# EndStop.net
KiCad netlist of a schematic drawn in EAGLE
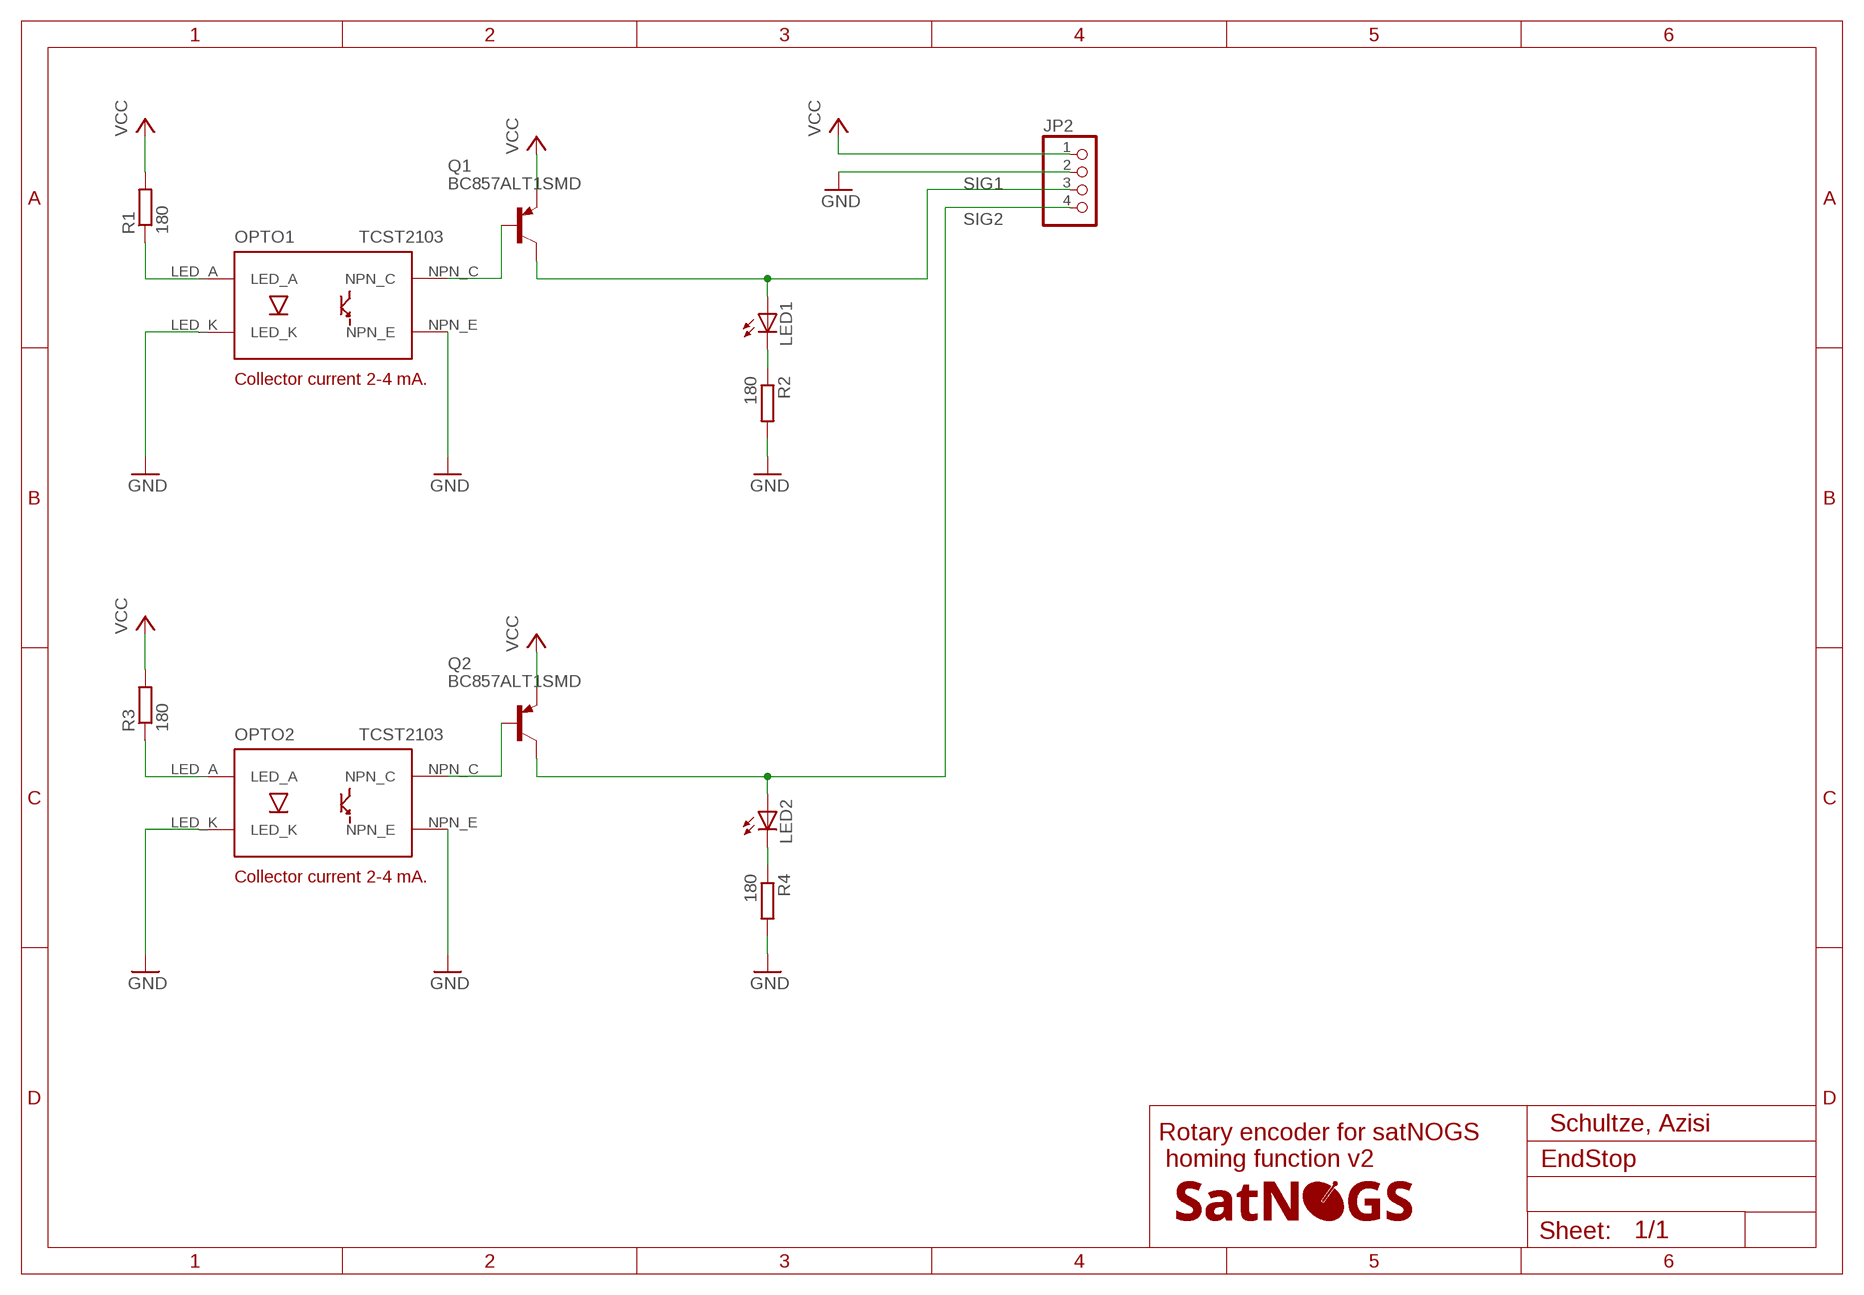
[diagram p0: schematic, sheet 1]

(export (version "E")
  (design (tool "Eeschema 10.0.6"))
  (components
    (comp (ref "JP2")
      (value "PINHD-1X4")
      (footprint "eagle-import:1X04")
      (libsource (lib "eagle-import") (part "PINHD-1X4"))
    )
    (comp (ref "LED1")
      (value "LED3MM")
      (footprint "eagle-import:LED3MM")
      (libsource (lib "eagle-import") (part "LED3MM"))
    )
    (comp (ref "LED2")
      (value "LED3MM")
      (footprint "eagle-import:LED3MM")
      (libsource (lib "eagle-import") (part "LED3MM"))
    )
    (comp (ref "LOGO1")
      (value "SATNOGS_LOGOSILK_XS")
      (footprint "eagle-import:LOGO_SILK_XS")
      (libsource (lib "eagle-import") (part "SATNOGS_LOGOSILK_XS"))
    )
    (comp (ref "OPTO1")
      (value "TCST2103")
      (footprint "eagle-import:TCST2013")
      (libsource (lib "eagle-import") (part "TCST2103"))
    )
    (comp (ref "OPTO2")
      (value "TCST2103")
      (footprint "eagle-import:TCST2013")
      (libsource (lib "eagle-import") (part "TCST2103"))
    )
    (comp (ref "Q1")
      (value "BC857ALT1SMD")
      (footprint "eagle-import:SOT23-BEC")
      (libsource (lib "eagle-import") (part "BC857SMDALT1"))
    )
    (comp (ref "Q2")
      (value "BC857ALT1SMD")
      (footprint "eagle-import:SOT23-BEC")
      (libsource (lib "eagle-import") (part "BC857SMDALT1"))
    )
    (comp (ref "R1")
      (value "180")
      (footprint "eagle-import:R0805")
      (libsource (lib "eagle-import") (part "R-EU_R0805"))
    )
    (comp (ref "R2")
      (value "180")
      (footprint "eagle-import:R0805")
      (libsource (lib "eagle-import") (part "R-EU_R0805"))
    )
    (comp (ref "R3")
      (value "180")
      (footprint "eagle-import:R0805")
      (libsource (lib "eagle-import") (part "R-EU_R0805"))
    )
    (comp (ref "R4")
      (value "180")
      (footprint "eagle-import:R0805")
      (libsource (lib "eagle-import") (part "R-EU_R0805"))
    )
  )
  (nets
    (net (code "1") (name "/SIG1") (class "Default")
      (node (ref "JP2") (pin "3") (pinfunction "3_3") (pintype "passive"))
      (node (ref "LED1") (pin "A") (pinfunction "A_A") (pintype "passive"))
      (node (ref "Q1") (pin "C") (pinfunction "C_C") (pintype "passive"))
    )
    (net (code "2") (name "/SIG2") (class "Default")
      (node (ref "JP2") (pin "4") (pinfunction "4_4") (pintype "passive"))
      (node (ref "LED2") (pin "A") (pinfunction "A_A") (pintype "passive"))
      (node (ref "Q2") (pin "C") (pinfunction "C_C") (pintype "passive"))
    )
    (net (code "3") (name "GND") (class "Default")
      (node (ref "JP2") (pin "2") (pinfunction "2_2") (pintype "passive"))
      (node (ref "OPTO1") (pin "LED_K") (pinfunction "LED_K_LED_K") (pintype "bidirectional"))
      (node (ref "OPTO1") (pin "NPN_E") (pinfunction "NPN_E_NPN_E") (pintype "bidirectional"))
      (node (ref "OPTO2") (pin "LED_K") (pinfunction "LED_K_LED_K") (pintype "bidirectional"))
      (node (ref "OPTO2") (pin "NPN_E") (pinfunction "NPN_E_NPN_E") (pintype "bidirectional"))
      (node (ref "R2") (pin "2") (pinfunction "2_2") (pintype "passive"))
      (node (ref "R4") (pin "2") (pinfunction "2_2") (pintype "passive"))
    )
    (net (code "4") (name "Net-(LED1-C)") (class "Default")
      (node (ref "LED1") (pin "K") (pinfunction "C_K") (pintype "passive"))
      (node (ref "R2") (pin "1") (pinfunction "1_1") (pintype "passive"))
    )
    (net (code "5") (name "Net-(LED2-C)") (class "Default")
      (node (ref "LED2") (pin "K") (pinfunction "C_K") (pintype "passive"))
      (node (ref "R4") (pin "1") (pinfunction "1_1") (pintype "passive"))
    )
    (net (code "6") (name "Net-(OPTO1-PadLED_A)") (class "Default")
      (node (ref "OPTO1") (pin "LED_A") (pinfunction "LED_A_LED_A") (pintype "bidirectional"))
      (node (ref "R1") (pin "1") (pinfunction "1_1") (pintype "passive"))
    )
    (net (code "7") (name "Net-(OPTO1-PadNPN_C)") (class "Default")
      (node (ref "OPTO1") (pin "NPN_C") (pinfunction "NPN_C_NPN_C") (pintype "bidirectional"))
      (node (ref "Q1") (pin "B") (pinfunction "B_B") (pintype "passive"))
    )
    (net (code "8") (name "Net-(OPTO2-PadLED_A)") (class "Default")
      (node (ref "OPTO2") (pin "LED_A") (pinfunction "LED_A_LED_A") (pintype "bidirectional"))
      (node (ref "R3") (pin "1") (pinfunction "1_1") (pintype "passive"))
    )
    (net (code "9") (name "Net-(OPTO2-PadNPN_C)") (class "Default")
      (node (ref "OPTO2") (pin "NPN_C") (pinfunction "NPN_C_NPN_C") (pintype "bidirectional"))
      (node (ref "Q2") (pin "B") (pinfunction "B_B") (pintype "passive"))
    )
    (net (code "10") (name "VCC") (class "Default")
      (node (ref "JP2") (pin "1") (pinfunction "1_1") (pintype "passive"))
      (node (ref "Q1") (pin "E") (pinfunction "E_E") (pintype "passive"))
      (node (ref "Q2") (pin "E") (pinfunction "E_E") (pintype "passive"))
      (node (ref "R1") (pin "2") (pinfunction "2_2") (pintype "passive"))
      (node (ref "R3") (pin "2") (pinfunction "2_2") (pintype "passive"))
    )
  )
)
